# wa_amp.net
KiCad netlist of a schematic drawn in EAGLE
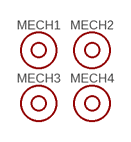
[diagram p0: schematic, sheet 1, part 1 of 2]
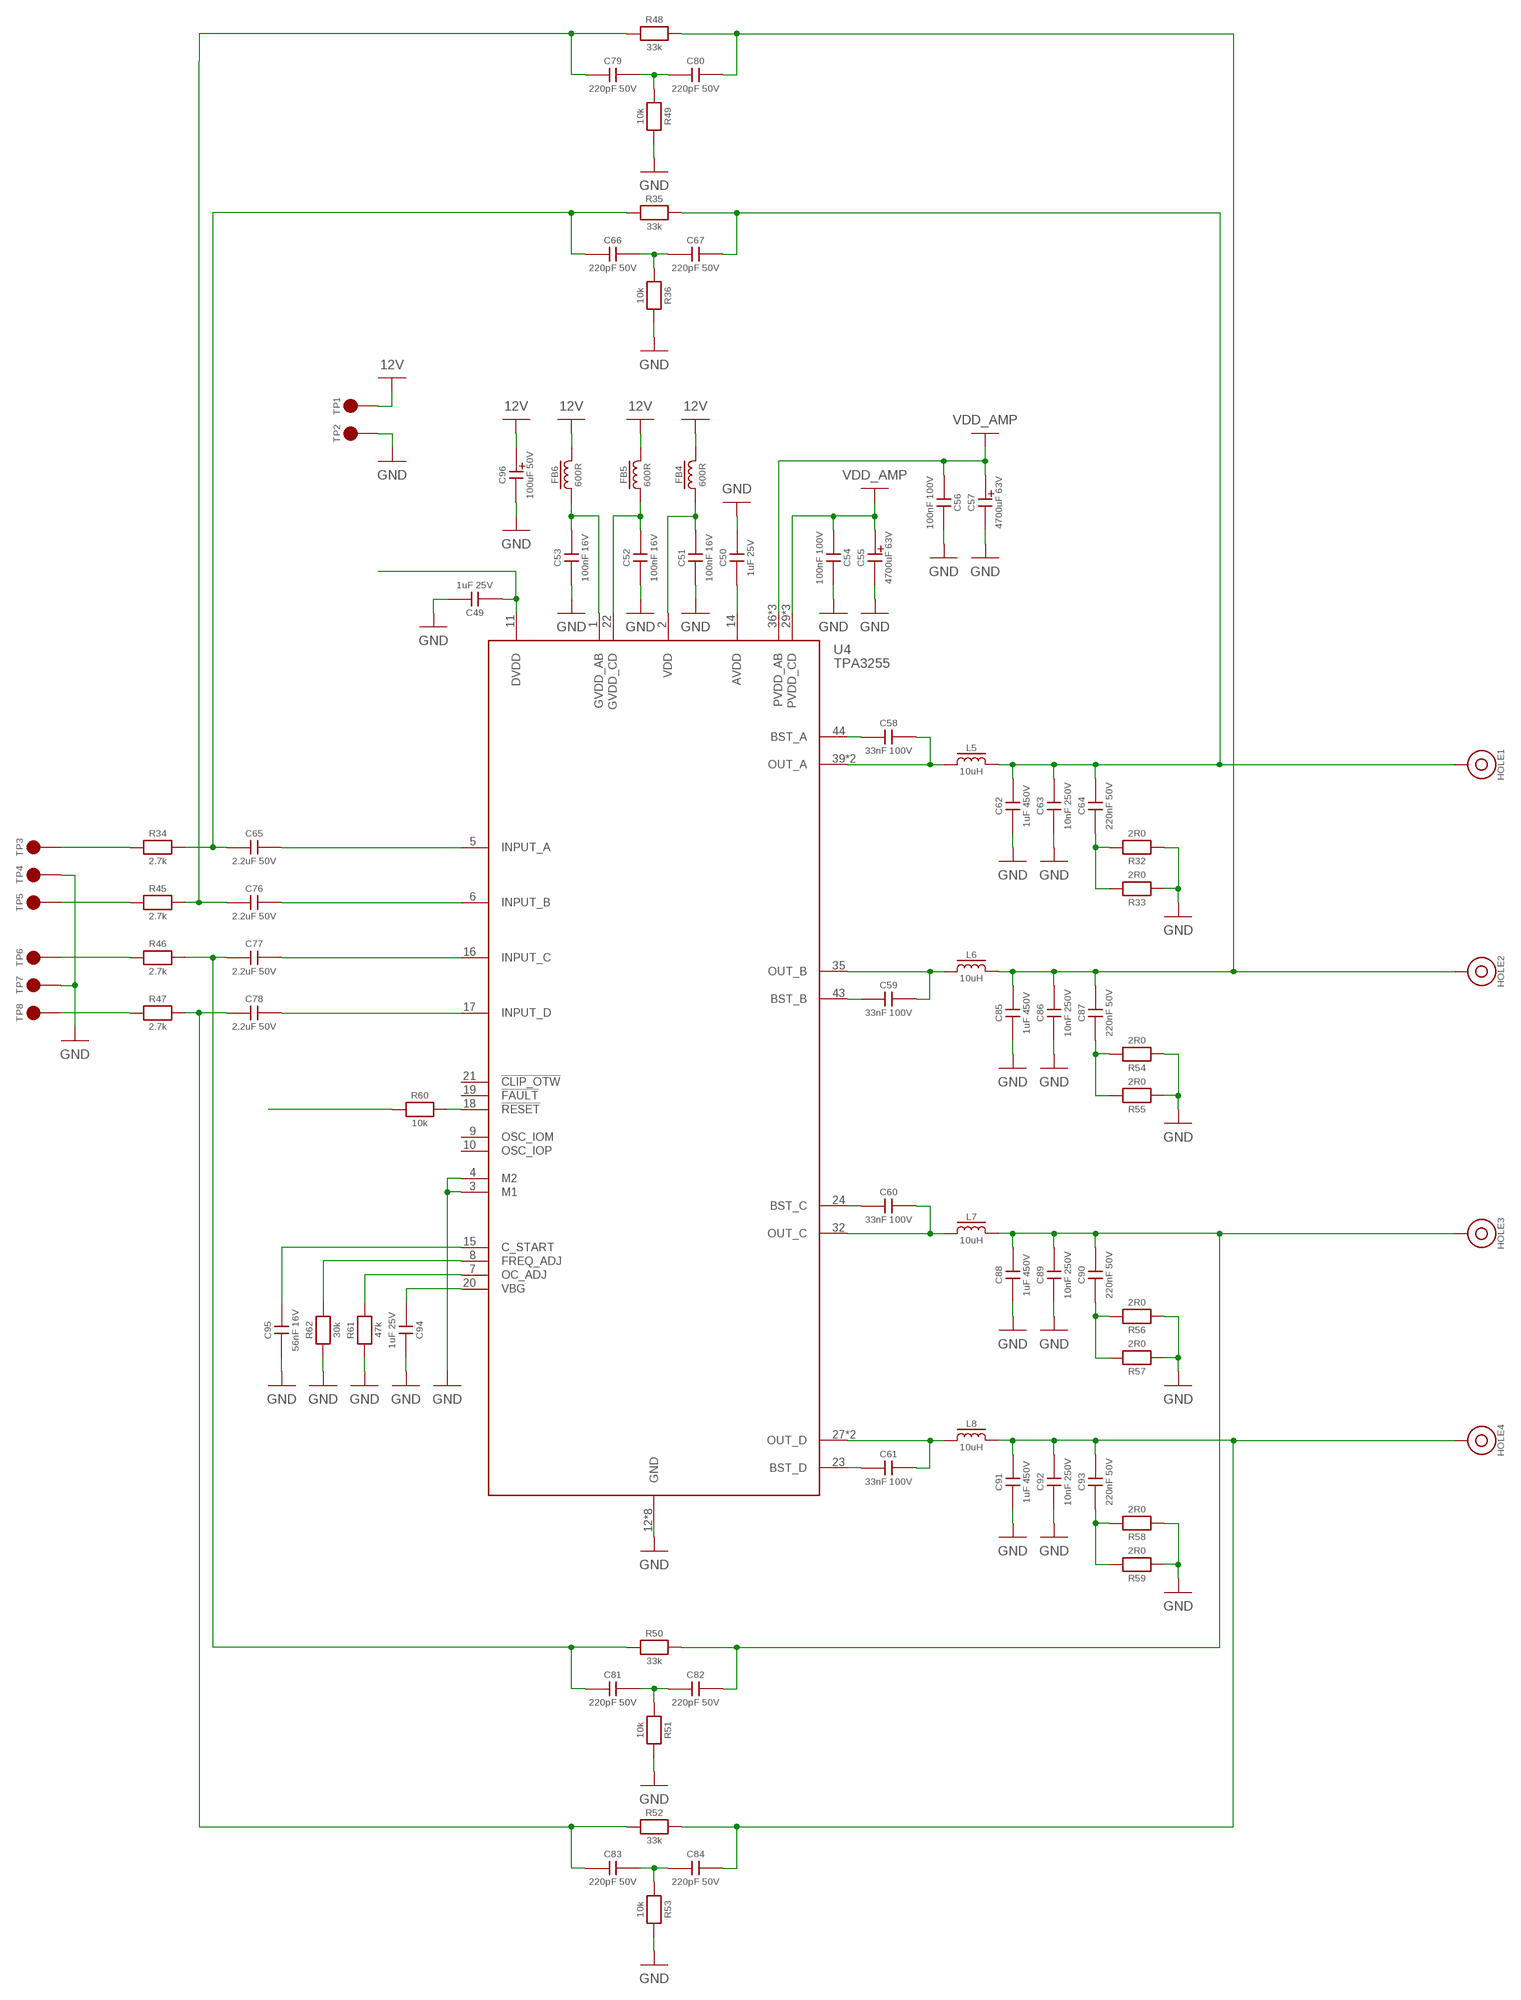
[diagram p1: schematic, sheet 1, part 2 of 2]

(export (version "E")
  (design (tool "Eeschema 10.0.6"))
  (components
    (comp (ref "C49")
      (value "1uF 25V")
      (footprint "eagle-import:0603")
      (libsource (lib "eagle-import") (part "CL10A105KA8NNNC"))
    )
    (comp (ref "C50")
      (value "1uF 25V")
      (footprint "eagle-import:0603")
      (libsource (lib "eagle-import") (part "CL10A105KA8NNNC"))
    )
    (comp (ref "C51")
      (value "100nF 16V")
      (footprint "eagle-import:0603")
      (libsource (lib "eagle-import") (part "CL10B104KO8WPNC"))
    )
    (comp (ref "C52")
      (value "100nF 16V")
      (footprint "eagle-import:0603")
      (libsource (lib "eagle-import") (part "CL10B104KO8WPNC"))
    )
    (comp (ref "C53")
      (value "100nF 16V")
      (footprint "eagle-import:0603")
      (libsource (lib "eagle-import") (part "CL10B104KO8WPNC"))
    )
    (comp (ref "C54")
      (value "100nF 100V")
      (footprint "eagle-import:0603")
      (libsource (lib "eagle-import") (part "06031C104KAT2A"))
    )
    (comp (ref "C55")
      (value "4700uF 63V")
      (footprint "eagle-import:30MM_RADIAL_10MM_PITCH")
      (libsource (lib "eagle-import") (part "B41231C8478M000"))
    )
    (comp (ref "C56")
      (value "100nF 100V")
      (footprint "eagle-import:0603")
      (libsource (lib "eagle-import") (part "06031C104KAT2A"))
    )
    (comp (ref "C57")
      (value "4700uF 63V")
      (footprint "eagle-import:30MM_RADIAL_10MM_PITCH")
      (libsource (lib "eagle-import") (part "B41231C8478M000"))
    )
    (comp (ref "C58")
      (value "33nF 100V")
      (footprint "eagle-import:0603")
      (libsource (lib "eagle-import") (part "C0603C333K1RACTU"))
    )
    (comp (ref "C59")
      (value "33nF 100V")
      (footprint "eagle-import:0603")
      (libsource (lib "eagle-import") (part "C0603C333K1RACTU"))
    )
    (comp (ref "C60")
      (value "33nF 100V")
      (footprint "eagle-import:0603")
      (libsource (lib "eagle-import") (part "C0603C333K1RACTU"))
    )
    (comp (ref "C61")
      (value "33nF 100V")
      (footprint "eagle-import:0603")
      (libsource (lib "eagle-import") (part "C0603C333K1RACTU"))
    )
    (comp (ref "C62")
      (value "1uF 450V")
      (footprint "eagle-import:7X17.5BOX")
      (libsource (lib "eagle-import") (part "ECWFE2W105K"))
    )
    (comp (ref "C63")
      (value "10nF 250V")
      (footprint "eagle-import:0603")
      (libsource (lib "eagle-import") (part "885342206006"))
    )
    (comp (ref "C64")
      (value "220nF 50V")
      (footprint "eagle-import:0603")
      (libsource (lib "eagle-import") (part "C1608X7R1H224K080AB"))
    )
    (comp (ref "C65")
      (value "2.2uF 50V")
      (footprint "eagle-import:5X7.2BOX")
      (libsource (lib "eagle-import") (part "MKS2B042201F00KSSD"))
    )
    (comp (ref "C66")
      (value "220pF 50V")
      (footprint "eagle-import:0603")
      (libsource (lib "eagle-import") (part "CC0603JRNPO9BN221"))
    )
    (comp (ref "C67")
      (value "220pF 50V")
      (footprint "eagle-import:0603")
      (libsource (lib "eagle-import") (part "CC0603JRNPO9BN221"))
    )
    (comp (ref "C76")
      (value "2.2uF 50V")
      (footprint "eagle-import:5X7.2BOX")
      (libsource (lib "eagle-import") (part "MKS2B042201F00KSSD"))
    )
    (comp (ref "C77")
      (value "2.2uF 50V")
      (footprint "eagle-import:5X7.2BOX")
      (libsource (lib "eagle-import") (part "MKS2B042201F00KSSD"))
    )
    (comp (ref "C78")
      (value "2.2uF 50V")
      (footprint "eagle-import:5X7.2BOX")
      (libsource (lib "eagle-import") (part "MKS2B042201F00KSSD"))
    )
    (comp (ref "C79")
      (value "220pF 50V")
      (footprint "eagle-import:0603")
      (libsource (lib "eagle-import") (part "CC0603JRNPO9BN221"))
    )
    (comp (ref "C80")
      (value "220pF 50V")
      (footprint "eagle-import:0603")
      (libsource (lib "eagle-import") (part "CC0603JRNPO9BN221"))
    )
    (comp (ref "C81")
      (value "220pF 50V")
      (footprint "eagle-import:0603")
      (libsource (lib "eagle-import") (part "CC0603JRNPO9BN221"))
    )
    (comp (ref "C82")
      (value "220pF 50V")
      (footprint "eagle-import:0603")
      (libsource (lib "eagle-import") (part "CC0603JRNPO9BN221"))
    )
    (comp (ref "C83")
      (value "220pF 50V")
      (footprint "eagle-import:0603")
      (libsource (lib "eagle-import") (part "CC0603JRNPO9BN221"))
    )
    (comp (ref "C84")
      (value "220pF 50V")
      (footprint "eagle-import:0603")
      (libsource (lib "eagle-import") (part "CC0603JRNPO9BN221"))
    )
    (comp (ref "C85")
      (value "1uF 450V")
      (footprint "eagle-import:7X17.5BOX")
      (libsource (lib "eagle-import") (part "ECWFE2W105K"))
    )
    (comp (ref "C86")
      (value "10nF 250V")
      (footprint "eagle-import:0603")
      (libsource (lib "eagle-import") (part "885342206006"))
    )
    (comp (ref "C87")
      (value "220nF 50V")
      (footprint "eagle-import:0603")
      (libsource (lib "eagle-import") (part "C1608X7R1H224K080AB"))
    )
    (comp (ref "C88")
      (value "1uF 450V")
      (footprint "eagle-import:7X17.5BOX")
      (libsource (lib "eagle-import") (part "ECWFE2W105K"))
    )
    (comp (ref "C89")
      (value "10nF 250V")
      (footprint "eagle-import:0603")
      (libsource (lib "eagle-import") (part "885342206006"))
    )
    (comp (ref "C90")
      (value "220nF 50V")
      (footprint "eagle-import:0603")
      (libsource (lib "eagle-import") (part "C1608X7R1H224K080AB"))
    )
    (comp (ref "C91")
      (value "1uF 450V")
      (footprint "eagle-import:7X17.5BOX")
      (libsource (lib "eagle-import") (part "ECWFE2W105K"))
    )
    (comp (ref "C92")
      (value "10nF 250V")
      (footprint "eagle-import:0603")
      (libsource (lib "eagle-import") (part "885342206006"))
    )
    (comp (ref "C93")
      (value "220nF 50V")
      (footprint "eagle-import:0603")
      (libsource (lib "eagle-import") (part "C1608X7R1H224K080AB"))
    )
    (comp (ref "C94")
      (value "1uF 25V")
      (footprint "eagle-import:0603")
      (libsource (lib "eagle-import") (part "CL10A105KA8NNNC"))
    )
    (comp (ref "C95")
      (value "56nF 16V")
      (footprint "eagle-import:0603")
      (libsource (lib "eagle-import") (part "GRM188R71C563JA01D"))
    )
    (comp (ref "C96")
      (value "100uF 50V")
      (footprint "eagle-import:8MM_RADIAL_3.5MM_PITCH")
      (libsource (lib "eagle-import") (part "107CKR050M"))
    )
    (comp (ref "FB4")
      (value "600R")
      (footprint "eagle-import:0603")
      (libsource (lib "eagle-import") (part "742792651"))
    )
    (comp (ref "FB5")
      (value "600R")
      (footprint "eagle-import:0603")
      (libsource (lib "eagle-import") (part "742792651"))
    )
    (comp (ref "FB6")
      (value "600R")
      (footprint "eagle-import:0603")
      (libsource (lib "eagle-import") (part "742792651"))
    )
    (comp (ref "HOLE1")
      (value "MOUNTHOLE_METAL6X3")
      (footprint "eagle-import:MOUNTHOLE_6X3_METAL")
      (libsource (lib "eagle-import") (part "MOUNTHOLE_METAL6X3"))
    )
    (comp (ref "HOLE2")
      (value "MOUNTHOLE_METAL6X3")
      (footprint "eagle-import:MOUNTHOLE_6X3_METAL")
      (libsource (lib "eagle-import") (part "MOUNTHOLE_METAL6X3"))
    )
    (comp (ref "HOLE3")
      (value "MOUNTHOLE_METAL6X3")
      (footprint "eagle-import:MOUNTHOLE_6X3_METAL")
      (libsource (lib "eagle-import") (part "MOUNTHOLE_METAL6X3"))
    )
    (comp (ref "HOLE4")
      (value "MOUNTHOLE_METAL6X3")
      (footprint "eagle-import:MOUNTHOLE_6X3_METAL")
      (libsource (lib "eagle-import") (part "MOUNTHOLE_METAL6X3"))
    )
    (comp (ref "L5")
      (value "10uH")
      (footprint "eagle-import:SRP1265A")
      (libsource (lib "eagle-import") (part "SRP1265A-100M"))
    )
    (comp (ref "L6")
      (value "10uH")
      (footprint "eagle-import:SRP1265A")
      (libsource (lib "eagle-import") (part "SRP1265A-100M"))
    )
    (comp (ref "L7")
      (value "10uH")
      (footprint "eagle-import:SRP1265A")
      (libsource (lib "eagle-import") (part "SRP1265A-100M"))
    )
    (comp (ref "L8")
      (value "10uH")
      (footprint "eagle-import:SRP1265A")
      (libsource (lib "eagle-import") (part "SRP1265A-100M"))
    )
    (comp (ref "MECH1")
      (value "6mm x 3mm")
      (footprint "eagle-import:MOUNTHOLE_6X3")
      (libsource (lib "eagle-import") (part "MOUNTHOLE"))
    )
    (comp (ref "MECH2")
      (value "6mm x 3mm")
      (footprint "eagle-import:MOUNTHOLE_6X3")
      (libsource (lib "eagle-import") (part "MOUNTHOLE"))
    )
    (comp (ref "MECH3")
      (value "6mm x 3mm")
      (footprint "eagle-import:MOUNTHOLE_6X3")
      (libsource (lib "eagle-import") (part "MOUNTHOLE"))
    )
    (comp (ref "MECH4")
      (value "6mm x 3mm")
      (footprint "eagle-import:MOUNTHOLE_6X3")
      (libsource (lib "eagle-import") (part "MOUNTHOLE"))
    )
    (comp (ref "R32")
      (value "2R0")
      (footprint "eagle-import:1206")
      (libsource (lib "eagle-import") (part "CRCW12062R00FNEA"))
    )
    (comp (ref "R33")
      (value "2R0")
      (footprint "eagle-import:1206")
      (libsource (lib "eagle-import") (part "CRCW12062R00FNEA"))
    )
    (comp (ref "R34")
      (value "2.7k")
      (footprint "eagle-import:0603")
      (libsource (lib "eagle-import") (part "ERJ3EKF2701V"))
    )
    (comp (ref "R35")
      (value "33k")
      (footprint "eagle-import:0603")
      (libsource (lib "eagle-import") (part "ERJ3EKF3302V"))
    )
    (comp (ref "R36")
      (value "10k")
      (footprint "eagle-import:0603")
      (libsource (lib "eagle-import") (part "ERJ3EKF1002V"))
    )
    (comp (ref "R45")
      (value "2.7k")
      (footprint "eagle-import:0603")
      (libsource (lib "eagle-import") (part "ERJ3EKF2701V"))
    )
    (comp (ref "R46")
      (value "2.7k")
      (footprint "eagle-import:0603")
      (libsource (lib "eagle-import") (part "ERJ3EKF2701V"))
    )
    (comp (ref "R47")
      (value "2.7k")
      (footprint "eagle-import:0603")
      (libsource (lib "eagle-import") (part "ERJ3EKF2701V"))
    )
    (comp (ref "R48")
      (value "33k")
      (footprint "eagle-import:0603")
      (libsource (lib "eagle-import") (part "ERJ3EKF3302V"))
    )
    (comp (ref "R49")
      (value "10k")
      (footprint "eagle-import:0603")
      (libsource (lib "eagle-import") (part "ERJ3EKF1002V"))
    )
    (comp (ref "R50")
      (value "33k")
      (footprint "eagle-import:0603")
      (libsource (lib "eagle-import") (part "ERJ3EKF3302V"))
    )
    (comp (ref "R51")
      (value "10k")
      (footprint "eagle-import:0603")
      (libsource (lib "eagle-import") (part "ERJ3EKF1002V"))
    )
    (comp (ref "R52")
      (value "33k")
      (footprint "eagle-import:0603")
      (libsource (lib "eagle-import") (part "ERJ3EKF3302V"))
    )
    (comp (ref "R53")
      (value "10k")
      (footprint "eagle-import:0603")
      (libsource (lib "eagle-import") (part "ERJ3EKF1002V"))
    )
    (comp (ref "R54")
      (value "2R0")
      (footprint "eagle-import:1206")
      (libsource (lib "eagle-import") (part "CRCW12062R00FNEA"))
    )
    (comp (ref "R55")
      (value "2R0")
      (footprint "eagle-import:1206")
      (libsource (lib "eagle-import") (part "CRCW12062R00FNEA"))
    )
    (comp (ref "R56")
      (value "2R0")
      (footprint "eagle-import:1206")
      (libsource (lib "eagle-import") (part "CRCW12062R00FNEA"))
    )
    (comp (ref "R57")
      (value "2R0")
      (footprint "eagle-import:1206")
      (libsource (lib "eagle-import") (part "CRCW12062R00FNEA"))
    )
    (comp (ref "R58")
      (value "2R0")
      (footprint "eagle-import:1206")
      (libsource (lib "eagle-import") (part "CRCW12062R00FNEA"))
    )
    (comp (ref "R59")
      (value "2R0")
      (footprint "eagle-import:1206")
      (libsource (lib "eagle-import") (part "CRCW12062R00FNEA"))
    )
    (comp (ref "R60")
      (value "10k")
      (footprint "eagle-import:0603")
      (libsource (lib "eagle-import") (part "ERJ3EKF1002V"))
    )
    (comp (ref "R61")
      (value "47k")
      (footprint "eagle-import:0603")
      (libsource (lib "eagle-import") (part "ERJ3EKF4702V"))
    )
    (comp (ref "R62")
      (value "30k")
      (footprint "eagle-import:0603")
      (libsource (lib "eagle-import") (part "ERJ3EKF3002V"))
    )
    (comp (ref "TP1")
      (value "2MM_TEST_POINT")
      (footprint "eagle-import:2MM_TEST_PAD")
      (libsource (lib "eagle-import") (part "2MM_TEST_POINT"))
    )
    (comp (ref "TP2")
      (value "2MM_TEST_POINT")
      (footprint "eagle-import:2MM_TEST_PAD")
      (libsource (lib "eagle-import") (part "2MM_TEST_POINT"))
    )
    (comp (ref "TP3")
      (value "2MM_TEST_POINT")
      (footprint "eagle-import:2MM_TEST_PAD")
      (libsource (lib "eagle-import") (part "2MM_TEST_POINT"))
    )
    (comp (ref "TP4")
      (value "2MM_TEST_POINT")
      (footprint "eagle-import:2MM_TEST_PAD")
      (libsource (lib "eagle-import") (part "2MM_TEST_POINT"))
    )
    (comp (ref "TP5")
      (value "2MM_TEST_POINT")
      (footprint "eagle-import:2MM_TEST_PAD")
      (libsource (lib "eagle-import") (part "2MM_TEST_POINT"))
    )
    (comp (ref "TP6")
      (value "2MM_TEST_POINT")
      (footprint "eagle-import:2MM_TEST_PAD")
      (libsource (lib "eagle-import") (part "2MM_TEST_POINT"))
    )
    (comp (ref "TP7")
      (value "2MM_TEST_POINT")
      (footprint "eagle-import:2MM_TEST_PAD")
      (libsource (lib "eagle-import") (part "2MM_TEST_POINT"))
    )
    (comp (ref "TP8")
      (value "2MM_TEST_POINT")
      (footprint "eagle-import:2MM_TEST_PAD")
      (libsource (lib "eagle-import") (part "2MM_TEST_POINT"))
    )
    (comp (ref "U4")
      (value "TPA3255")
      (footprint "eagle-import:HTSSOP44")
      (libsource (lib "eagle-import") (part "TPA3255"))
    )
  )
  (nets
    (net (code "1") (name "/TPA_VDD_1") (class "Default")
      (node (ref "C49") (pin "1") (pinfunction "1_1") (pintype "bidirectional"))
      (node (ref "R60") (pin "1") (pinfunction "1_1") (pintype "bidirectional"))
      (node (ref "U4") (pin "11") (pinfunction "DVDD_11") (pintype "bidirectional"))
    )
    (net (code "2") (name "12V") (class "Default")
      (node (ref "C96") (pin "P") (pinfunction "A_P") (pintype "bidirectional"))
      (node (ref "FB4") (pin "2") (pinfunction "2_2") (pintype "bidirectional"))
      (node (ref "FB5") (pin "2") (pinfunction "2_2") (pintype "bidirectional"))
      (node (ref "FB6") (pin "2") (pinfunction "2_2") (pintype "bidirectional"))
      (node (ref "TP1") (pin "1") (pinfunction "P$1_1") (pintype "bidirectional"))
    )
    (net (code "3") (name "GND") (class "Default")
      (node (ref "C49") (pin "2") (pinfunction "2_2") (pintype "bidirectional"))
      (node (ref "C50") (pin "2") (pinfunction "2_2") (pintype "bidirectional"))
      (node (ref "C51") (pin "1") (pinfunction "1_1") (pintype "bidirectional"))
      (node (ref "C52") (pin "1") (pinfunction "1_1") (pintype "bidirectional"))
      (node (ref "C53") (pin "1") (pinfunction "1_1") (pintype "bidirectional"))
      (node (ref "C54") (pin "2") (pinfunction "2_2") (pintype "bidirectional"))
      (node (ref "C55") (pin "1") (pinfunction "K_1") (pintype "bidirectional"))
      (node (ref "C56") (pin "2") (pinfunction "2_2") (pintype "bidirectional"))
      (node (ref "C57") (pin "1") (pinfunction "K_1") (pintype "bidirectional"))
      (node (ref "C62") (pin "1") (pinfunction "1_1") (pintype "bidirectional"))
      (node (ref "C63") (pin "1") (pinfunction "1_1") (pintype "bidirectional"))
      (node (ref "C85") (pin "1") (pinfunction "1_1") (pintype "bidirectional"))
      (node (ref "C86") (pin "1") (pinfunction "1_1") (pintype "bidirectional"))
      (node (ref "C88") (pin "1") (pinfunction "1_1") (pintype "bidirectional"))
      (node (ref "C89") (pin "1") (pinfunction "1_1") (pintype "bidirectional"))
      (node (ref "C91") (pin "1") (pinfunction "1_1") (pintype "bidirectional"))
      (node (ref "C92") (pin "1") (pinfunction "1_1") (pintype "bidirectional"))
      (node (ref "C94") (pin "2") (pinfunction "2_2") (pintype "bidirectional"))
      (node (ref "C95") (pin "1") (pinfunction "1_1") (pintype "bidirectional"))
      (node (ref "C96") (pin "N") (pinfunction "K_N") (pintype "bidirectional"))
      (node (ref "R32") (pin "1") (pinfunction "1_1") (pintype "bidirectional"))
      (node (ref "R33") (pin "1") (pinfunction "1_1") (pintype "bidirectional"))
      (node (ref "R36") (pin "2") (pinfunction "2_2") (pintype "bidirectional"))
      (node (ref "R49") (pin "2") (pinfunction "2_2") (pintype "bidirectional"))
      (node (ref "R51") (pin "2") (pinfunction "2_2") (pintype "bidirectional"))
      (node (ref "R53") (pin "2") (pinfunction "2_2") (pintype "bidirectional"))
      (node (ref "R54") (pin "1") (pinfunction "1_1") (pintype "bidirectional"))
      (node (ref "R55") (pin "1") (pinfunction "1_1") (pintype "bidirectional"))
      (node (ref "R56") (pin "1") (pinfunction "1_1") (pintype "bidirectional"))
      (node (ref "R57") (pin "1") (pinfunction "1_1") (pintype "bidirectional"))
      (node (ref "R58") (pin "1") (pinfunction "1_1") (pintype "bidirectional"))
      (node (ref "R59") (pin "1") (pinfunction "1_1") (pintype "bidirectional"))
      (node (ref "R61") (pin "1") (pinfunction "1_1") (pintype "bidirectional"))
      (node (ref "R62") (pin "1") (pinfunction "1_1") (pintype "bidirectional"))
      (node (ref "TP2") (pin "1") (pinfunction "P$1_1") (pintype "bidirectional"))
      (node (ref "TP4") (pin "1") (pinfunction "P$1_1") (pintype "bidirectional"))
      (node (ref "TP7") (pin "1") (pinfunction "P$1_1") (pintype "bidirectional"))
      (node (ref "U4") (pin "12") (pinfunction "GND_12") (pintype "bidirectional"))
      (node (ref "U4") (pin "13") (pinfunction "GND_13") (pintype "bidirectional"))
      (node (ref "U4") (pin "25") (pinfunction "GND_25") (pintype "bidirectional"))
      (node (ref "U4") (pin "26") (pinfunction "GND_26") (pintype "bidirectional"))
      (node (ref "U4") (pin "3") (pinfunction "M1_3") (pintype "bidirectional"))
      (node (ref "U4") (pin "33") (pinfunction "GND_33") (pintype "bidirectional"))
      (node (ref "U4") (pin "34") (pinfunction "GND_34") (pintype "bidirectional"))
      (node (ref "U4") (pin "4") (pinfunction "M2_4") (pintype "bidirectional"))
      (node (ref "U4") (pin "41") (pinfunction "GND_41") (pintype "bidirectional"))
      (node (ref "U4") (pin "42") (pinfunction "GND_42") (pintype "bidirectional"))
    )
    (net (code "4") (name "Net-(C58-Pad2)") (class "Default")
      (node (ref "C58") (pin "2") (pinfunction "2_2") (pintype "bidirectional"))
      (node (ref "L5") (pin "1") (pinfunction "1_1") (pintype "bidirectional"))
      (node (ref "U4") (pin "39") (pinfunction "OUT_A_39") (pintype "bidirectional"))
      (node (ref "U4") (pin "40") (pinfunction "OUT_A_40") (pintype "bidirectional"))
    )
    (net (code "5") (name "Net-(C61-Pad2)") (class "Default")
      (node (ref "C61") (pin "2") (pinfunction "2_2") (pintype "bidirectional"))
      (node (ref "L8") (pin "1") (pinfunction "1_1") (pintype "bidirectional"))
      (node (ref "U4") (pin "27") (pinfunction "OUT_D_27") (pintype "bidirectional"))
      (node (ref "U4") (pin "28") (pinfunction "OUT_D_28") (pintype "bidirectional"))
    )
    (net (code "6") (name "Net-(C64-Pad1)") (class "Default")
      (node (ref "C64") (pin "1") (pinfunction "1_1") (pintype "bidirectional"))
      (node (ref "R32") (pin "2") (pinfunction "2_2") (pintype "bidirectional"))
      (node (ref "R33") (pin "2") (pinfunction "2_2") (pintype "bidirectional"))
    )
    (net (code "7") (name "Net-(C65-Pad1)") (class "Default")
      (node (ref "C65") (pin "1") (pinfunction "1_1") (pintype "bidirectional"))
      (node (ref "C66") (pin "1") (pinfunction "1_1") (pintype "bidirectional"))
      (node (ref "R34") (pin "2") (pinfunction "2_2") (pintype "bidirectional"))
      (node (ref "R35") (pin "1") (pinfunction "1_1") (pintype "bidirectional"))
    )
    (net (code "8") (name "Net-(C66-Pad2)") (class "Default")
      (node (ref "C66") (pin "2") (pinfunction "2_2") (pintype "bidirectional"))
      (node (ref "C67") (pin "1") (pinfunction "1_1") (pintype "bidirectional"))
      (node (ref "R36") (pin "1") (pinfunction "1_1") (pintype "bidirectional"))
    )
    (net (code "9") (name "Net-(C76-Pad1)") (class "Default")
      (node (ref "C76") (pin "1") (pinfunction "1_1") (pintype "bidirectional"))
      (node (ref "C79") (pin "1") (pinfunction "1_1") (pintype "bidirectional"))
      (node (ref "R45") (pin "2") (pinfunction "2_2") (pintype "bidirectional"))
      (node (ref "R48") (pin "1") (pinfunction "1_1") (pintype "bidirectional"))
    )
    (net (code "10") (name "Net-(C77-Pad1)") (class "Default")
      (node (ref "C77") (pin "1") (pinfunction "1_1") (pintype "bidirectional"))
      (node (ref "C81") (pin "1") (pinfunction "1_1") (pintype "bidirectional"))
      (node (ref "R46") (pin "2") (pinfunction "2_2") (pintype "bidirectional"))
      (node (ref "R50") (pin "1") (pinfunction "1_1") (pintype "bidirectional"))
    )
    (net (code "11") (name "Net-(C78-Pad1)") (class "Default")
      (node (ref "C78") (pin "1") (pinfunction "1_1") (pintype "bidirectional"))
      (node (ref "C83") (pin "1") (pinfunction "1_1") (pintype "bidirectional"))
      (node (ref "R47") (pin "2") (pinfunction "2_2") (pintype "bidirectional"))
      (node (ref "R52") (pin "1") (pinfunction "1_1") (pintype "bidirectional"))
    )
    (net (code "12") (name "Net-(C79-Pad2)") (class "Default")
      (node (ref "C79") (pin "2") (pinfunction "2_2") (pintype "bidirectional"))
      (node (ref "C80") (pin "1") (pinfunction "1_1") (pintype "bidirectional"))
      (node (ref "R49") (pin "1") (pinfunction "1_1") (pintype "bidirectional"))
    )
    (net (code "13") (name "Net-(C81-Pad2)") (class "Default")
      (node (ref "C81") (pin "2") (pinfunction "2_2") (pintype "bidirectional"))
      (node (ref "C82") (pin "1") (pinfunction "1_1") (pintype "bidirectional"))
      (node (ref "R51") (pin "1") (pinfunction "1_1") (pintype "bidirectional"))
    )
    (net (code "14") (name "Net-(C83-Pad2)") (class "Default")
      (node (ref "C83") (pin "2") (pinfunction "2_2") (pintype "bidirectional"))
      (node (ref "C84") (pin "1") (pinfunction "1_1") (pintype "bidirectional"))
      (node (ref "R53") (pin "1") (pinfunction "1_1") (pintype "bidirectional"))
    )
    (net (code "15") (name "Net-(C87-Pad1)") (class "Default")
      (node (ref "C87") (pin "1") (pinfunction "1_1") (pintype "bidirectional"))
      (node (ref "R54") (pin "2") (pinfunction "2_2") (pintype "bidirectional"))
      (node (ref "R55") (pin "2") (pinfunction "2_2") (pintype "bidirectional"))
    )
    (net (code "16") (name "Net-(C90-Pad1)") (class "Default")
      (node (ref "C90") (pin "1") (pinfunction "1_1") (pintype "bidirectional"))
      (node (ref "R56") (pin "2") (pinfunction "2_2") (pintype "bidirectional"))
      (node (ref "R57") (pin "2") (pinfunction "2_2") (pintype "bidirectional"))
    )
    (net (code "17") (name "Net-(C93-Pad1)") (class "Default")
      (node (ref "C93") (pin "1") (pinfunction "1_1") (pintype "bidirectional"))
      (node (ref "R58") (pin "2") (pinfunction "2_2") (pintype "bidirectional"))
      (node (ref "R59") (pin "2") (pinfunction "2_2") (pintype "bidirectional"))
    )
    (net (code "18") (name "Net-(HOLE1-1)") (class "Default")
      (node (ref "C62") (pin "2") (pinfunction "2_2") (pintype "bidirectional"))
      (node (ref "C63") (pin "2") (pinfunction "2_2") (pintype "bidirectional"))
      (node (ref "C64") (pin "2") (pinfunction "2_2") (pintype "bidirectional"))
      (node (ref "C67") (pin "2") (pinfunction "2_2") (pintype "bidirectional"))
      (node (ref "HOLE1") (pin "P$1") (pinfunction "1_P$1") (pintype "bidirectional"))
      (node (ref "L5") (pin "2") (pinfunction "2_2") (pintype "bidirectional"))
      (node (ref "R35") (pin "2") (pinfunction "2_2") (pintype "bidirectional"))
    )
    (net (code "19") (name "Net-(HOLE2-1)") (class "Default")
      (node (ref "C80") (pin "2") (pinfunction "2_2") (pintype "bidirectional"))
      (node (ref "C85") (pin "2") (pinfunction "2_2") (pintype "bidirectional"))
      (node (ref "C86") (pin "2") (pinfunction "2_2") (pintype "bidirectional"))
      (node (ref "C87") (pin "2") (pinfunction "2_2") (pintype "bidirectional"))
      (node (ref "HOLE2") (pin "P$1") (pinfunction "1_P$1") (pintype "bidirectional"))
      (node (ref "L6") (pin "2") (pinfunction "2_2") (pintype "bidirectional"))
      (node (ref "R48") (pin "2") (pinfunction "2_2") (pintype "bidirectional"))
    )
    (net (code "20") (name "Net-(HOLE3-1)") (class "Default")
      (node (ref "C82") (pin "2") (pinfunction "2_2") (pintype "bidirectional"))
      (node (ref "C88") (pin "2") (pinfunction "2_2") (pintype "bidirectional"))
      (node (ref "C89") (pin "2") (pinfunction "2_2") (pintype "bidirectional"))
      (node (ref "C90") (pin "2") (pinfunction "2_2") (pintype "bidirectional"))
      (node (ref "HOLE3") (pin "P$1") (pinfunction "1_P$1") (pintype "bidirectional"))
      (node (ref "L7") (pin "2") (pinfunction "2_2") (pintype "bidirectional"))
      (node (ref "R50") (pin "2") (pinfunction "2_2") (pintype "bidirectional"))
    )
    (net (code "21") (name "Net-(HOLE4-1)") (class "Default")
      (node (ref "C84") (pin "2") (pinfunction "2_2") (pintype "bidirectional"))
      (node (ref "C91") (pin "2") (pinfunction "2_2") (pintype "bidirectional"))
      (node (ref "C92") (pin "2") (pinfunction "2_2") (pintype "bidirectional"))
      (node (ref "C93") (pin "2") (pinfunction "2_2") (pintype "bidirectional"))
      (node (ref "HOLE4") (pin "P$1") (pinfunction "1_P$1") (pintype "bidirectional"))
      (node (ref "L8") (pin "2") (pinfunction "2_2") (pintype "bidirectional"))
      (node (ref "R52") (pin "2") (pinfunction "2_2") (pintype "bidirectional"))
    )
    (net (code "22") (name "Net-(TP3-P$1)") (class "Default")
      (node (ref "R34") (pin "1") (pinfunction "1_1") (pintype "bidirectional"))
      (node (ref "TP3") (pin "1") (pinfunction "P$1_1") (pintype "bidirectional"))
    )
    (net (code "23") (name "Net-(TP5-P$1)") (class "Default")
      (node (ref "R45") (pin "1") (pinfunction "1_1") (pintype "bidirectional"))
      (node (ref "TP5") (pin "1") (pinfunction "P$1_1") (pintype "bidirectional"))
    )
    (net (code "24") (name "Net-(TP6-P$1)") (class "Default")
      (node (ref "R46") (pin "1") (pinfunction "1_1") (pintype "bidirectional"))
      (node (ref "TP6") (pin "1") (pinfunction "P$1_1") (pintype "bidirectional"))
    )
    (net (code "25") (name "Net-(TP8-P$1)") (class "Default")
      (node (ref "R47") (pin "1") (pinfunction "1_1") (pintype "bidirectional"))
      (node (ref "TP8") (pin "1") (pinfunction "P$1_1") (pintype "bidirectional"))
    )
    (net (code "26") (name "Net-(U4-AVDD)") (class "Default")
      (node (ref "C50") (pin "1") (pinfunction "1_1") (pintype "bidirectional"))
      (node (ref "U4") (pin "14") (pinfunction "AVDD_14") (pintype "bidirectional"))
    )
    (net (code "27") (name "Net-(U4-BST_A)") (class "Default")
      (node (ref "C58") (pin "1") (pinfunction "1_1") (pintype "bidirectional"))
      (node (ref "U4") (pin "44") (pinfunction "BST_A_44") (pintype "bidirectional"))
    )
    (net (code "28") (name "Net-(U4-BST_B)") (class "Default")
      (node (ref "C59") (pin "1") (pinfunction "1_1") (pintype "bidirectional"))
      (node (ref "U4") (pin "43") (pinfunction "BST_B_43") (pintype "bidirectional"))
    )
    (net (code "29") (name "Net-(U4-BST_C)") (class "Default")
      (node (ref "C60") (pin "1") (pinfunction "1_1") (pintype "bidirectional"))
      (node (ref "U4") (pin "24") (pinfunction "BST_C_24") (pintype "bidirectional"))
    )
    (net (code "30") (name "Net-(U4-BST_D)") (class "Default")
      (node (ref "C61") (pin "1") (pinfunction "1_1") (pintype "bidirectional"))
      (node (ref "U4") (pin "23") (pinfunction "BST_D_23") (pintype "bidirectional"))
    )
    (net (code "31") (name "Net-(U4-C_START)") (class "Default")
      (node (ref "C95") (pin "2") (pinfunction "2_2") (pintype "bidirectional"))
      (node (ref "U4") (pin "15") (pinfunction "C_START_15") (pintype "bidirectional"))
    )
    (net (code "32") (name "Net-(U4-FREQ_ADJ)") (class "Default")
      (node (ref "R62") (pin "2") (pinfunction "2_2") (pintype "bidirectional"))
      (node (ref "U4") (pin "8") (pinfunction "FREQ_ADJ_8") (pintype "bidirectional"))
    )
    (net (code "33") (name "Net-(U4-GVDD_AB)") (class "Default")
      (node (ref "C53") (pin "2") (pinfunction "2_2") (pintype "bidirectional"))
      (node (ref "FB6") (pin "1") (pinfunction "1_1") (pintype "bidirectional"))
      (node (ref "U4") (pin "1") (pinfunction "GVDD_AB_1") (pintype "bidirectional"))
    )
    (net (code "34") (name "Net-(U4-GVDD_CD)") (class "Default")
      (node (ref "C52") (pin "2") (pinfunction "2_2") (pintype "bidirectional"))
      (node (ref "FB5") (pin "1") (pinfunction "1_1") (pintype "bidirectional"))
      (node (ref "U4") (pin "22") (pinfunction "GVDD_CD_22") (pintype "bidirectional"))
    )
    (net (code "35") (name "Net-(U4-INPUT_A)") (class "Default")
      (node (ref "C65") (pin "2") (pinfunction "2_2") (pintype "bidirectional"))
      (node (ref "U4") (pin "5") (pinfunction "INPUT_A_5") (pintype "bidirectional"))
    )
    (net (code "36") (name "Net-(U4-INPUT_B)") (class "Default")
      (node (ref "C76") (pin "2") (pinfunction "2_2") (pintype "bidirectional"))
      (node (ref "U4") (pin "6") (pinfunction "INPUT_B_6") (pintype "bidirectional"))
    )
    (net (code "37") (name "Net-(U4-INPUT_C)") (class "Default")
      (node (ref "C77") (pin "2") (pinfunction "2_2") (pintype "bidirectional"))
      (node (ref "U4") (pin "16") (pinfunction "INPUT_C_16") (pintype "bidirectional"))
    )
    (net (code "38") (name "Net-(U4-INPUT_D)") (class "Default")
      (node (ref "C78") (pin "2") (pinfunction "2_2") (pintype "bidirectional"))
      (node (ref "U4") (pin "17") (pinfunction "INPUT_D_17") (pintype "bidirectional"))
    )
    (net (code "39") (name "Net-(U4-OC_ADJ)") (class "Default")
      (node (ref "R61") (pin "2") (pinfunction "2_2") (pintype "bidirectional"))
      (node (ref "U4") (pin "7") (pinfunction "OC_ADJ_7") (pintype "bidirectional"))
    )
    (net (code "40") (name "Net-(U4-OUT_B)") (class "Default")
      (node (ref "C59") (pin "2") (pinfunction "2_2") (pintype "bidirectional"))
      (node (ref "L6") (pin "1") (pinfunction "1_1") (pintype "bidirectional"))
      (node (ref "U4") (pin "35") (pinfunction "OUT_B_35") (pintype "bidirectional"))
    )
    (net (code "41") (name "Net-(U4-OUT_C)") (class "Default")
      (node (ref "C60") (pin "2") (pinfunction "2_2") (pintype "bidirectional"))
      (node (ref "L7") (pin "1") (pinfunction "1_1") (pintype "bidirectional"))
      (node (ref "U4") (pin "32") (pinfunction "OUT_C_32") (pintype "bidirectional"))
    )
    (net (code "42") (name "Net-(U4-VBG)") (class "Default")
      (node (ref "C94") (pin "1") (pinfunction "1_1") (pintype "bidirectional"))
      (node (ref "U4") (pin "20") (pinfunction "VBG_20") (pintype "bidirectional"))
    )
    (net (code "43") (name "Net-(U4-VDD)") (class "Default")
      (node (ref "C51") (pin "2") (pinfunction "2_2") (pintype "bidirectional"))
      (node (ref "FB4") (pin "1") (pinfunction "1_1") (pintype "bidirectional"))
      (node (ref "U4") (pin "2") (pinfunction "VDD_2") (pintype "bidirectional"))
    )
    (net (code "44") (name "Net-(U4-~{RESET})") (class "Default")
      (node (ref "R60") (pin "2") (pinfunction "2_2") (pintype "bidirectional"))
      (node (ref "U4") (pin "18") (pinfunction "~{RESET}_18") (pintype "bidirectional"))
    )
    (net (code "45") (name "VDD_AMP") (class "Default")
      (node (ref "C54") (pin "1") (pinfunction "1_1") (pintype "bidirectional"))
      (node (ref "C55") (pin "2") (pinfunction "A_2") (pintype "bidirectional"))
      (node (ref "C56") (pin "1") (pinfunction "1_1") (pintype "bidirectional"))
      (node (ref "C57") (pin "2") (pinfunction "A_2") (pintype "bidirectional"))
      (node (ref "U4") (pin "29") (pinfunction "PVDD_CD_29") (pintype "bidirectional"))
      (node (ref "U4") (pin "30") (pinfunction "PVDD_CD_30") (pintype "bidirectional"))
      (node (ref "U4") (pin "31") (pinfunction "PVDD_CD_31") (pintype "bidirectional"))
      (node (ref "U4") (pin "36") (pinfunction "PVDD_AB_36") (pintype "bidirectional"))
      (node (ref "U4") (pin "37") (pinfunction "PVDD_AB_37") (pintype "bidirectional"))
      (node (ref "U4") (pin "38") (pinfunction "PVDD_AB_38") (pintype "bidirectional"))
    )
    (net (code "46") (name "unconnected-(U4-OSC_IOM-Pad9)") (class "Default")
      (node (ref "U4") (pin "9") (pinfunction "OSC_IOM_9") (pintype "bidirectional"))
    )
    (net (code "47") (name "unconnected-(U4-OSC_IOP-Pad10)") (class "Default")
      (node (ref "U4") (pin "10") (pinfunction "OSC_IOP_10") (pintype "bidirectional"))
    )
    (net (code "48") (name "unconnected-(U4-~{CLIP_OTW}-Pad21)") (class "Default")
      (node (ref "U4") (pin "21") (pinfunction "~{CLIP_OTW}_21") (pintype "bidirectional"))
    )
    (net (code "49") (name "unconnected-(U4-~{FAULT}-Pad19)") (class "Default")
      (node (ref "U4") (pin "19") (pinfunction "~{FAULT}_19") (pintype "bidirectional"))
    )
  )
)
